# vf_zes.net
KiCad netlist of a schematic drawn in EAGLE
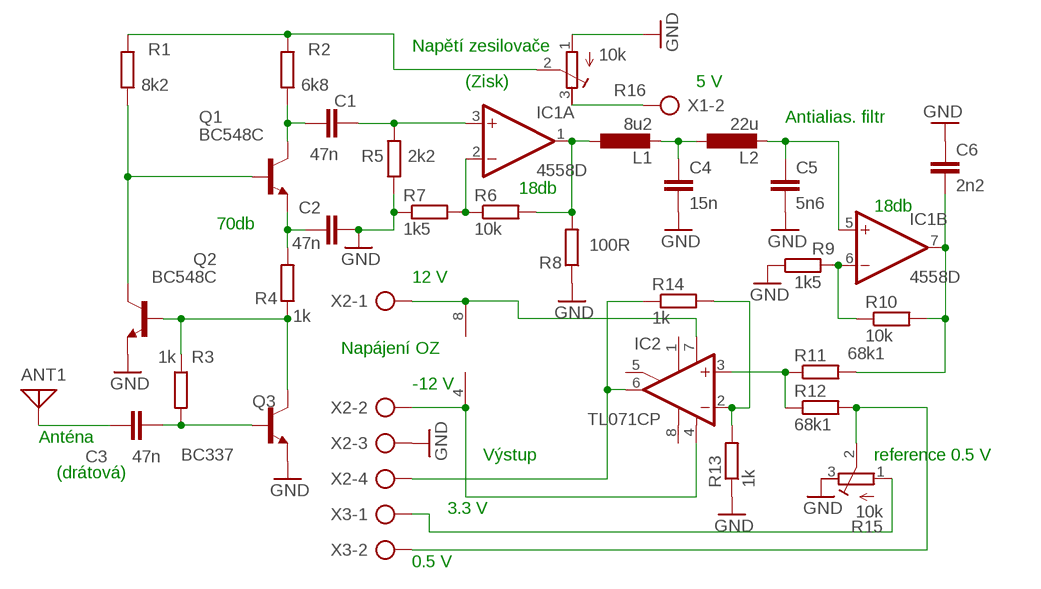
[diagram p0: schematic, sheet 1]

(export (version "E")
  (design (tool "Eeschema 10.0.6"))
  (components
    (comp (ref "ANT1")
      (value "ANTENNA")
      (footprint "eagle-import:PAD-01")
      (libsource (lib "eagle-import") (part "ANTENNA"))
    )
    (comp (ref "C1")
      (value "47n")
      (footprint "eagle-import:C025-025X050")
      (libsource (lib "eagle-import") (part "resistor_C-EU025-025X050"))
    )
    (comp (ref "C2")
      (value "47n")
      (footprint "eagle-import:C025-025X050")
      (libsource (lib "eagle-import") (part "resistor_C-EU025-025X050"))
    )
    (comp (ref "C3")
      (value "47n")
      (footprint "eagle-import:C025-025X050")
      (libsource (lib "eagle-import") (part "resistor_C-EU025-025X050"))
    )
    (comp (ref "C4")
      (value "15n")
      (footprint "eagle-import:C050-025X075")
      (libsource (lib "eagle-import") (part "C-EU050-025X075"))
    )
    (comp (ref "C5")
      (value "5n6")
      (footprint "eagle-import:C050-025X075")
      (libsource (lib "eagle-import") (part "C-EU050-025X075"))
    )
    (comp (ref "C6")
      (value "2n2")
      (footprint "eagle-import:C050-030X075")
      (libsource (lib "eagle-import") (part "C-EU050-030X075"))
    )
    (comp (ref "IC1")
      (value "4558D")
      (footprint "eagle-import:DIL08")
      (libsource (lib "eagle-import") (part "LF442N"))
    )
    (comp (ref "IC2")
      (value "TL071CP")
      (footprint "eagle-import:DIL08")
      (libsource (lib "eagle-import") (part "TL071P"))
    )
    (comp (ref "L1")
      (value "8u2")
      (footprint "eagle-import:0207_12")
      (libsource (lib "eagle-import") (part "L-EU0207/12"))
    )
    (comp (ref "L2")
      (value "22u")
      (footprint "eagle-import:0207_12")
      (libsource (lib "eagle-import") (part "L-EU0207/12"))
    )
    (comp (ref "Q1")
      (value "BC548C")
      (footprint "eagle-import:TO92-EBC")
      (libsource (lib "eagle-import") (part "BC548A"))
    )
    (comp (ref "Q2")
      (value "BC548C")
      (footprint "eagle-import:TO92-EBC")
      (libsource (lib "eagle-import") (part "BC548A"))
    )
    (comp (ref "Q3")
      (value "BC337")
      (footprint "eagle-import:TO92-EBC")
      (libsource (lib "eagle-import") (part "BC548A"))
    )
    (comp (ref "R1")
      (value "8k2")
      (footprint "eagle-import:0207_10")
      (libsource (lib "eagle-import") (part "resistor_R-EU_0207/10"))
    )
    (comp (ref "R2")
      (value "6k8")
      (footprint "eagle-import:0207_10")
      (libsource (lib "eagle-import") (part "resistor_R-EU_0207/10"))
    )
    (comp (ref "R3")
      (value "1k")
      (footprint "eagle-import:0207_10")
      (libsource (lib "eagle-import") (part "resistor_R-EU_0207/10"))
    )
    (comp (ref "R4")
      (value "1k")
      (footprint "eagle-import:0207_10")
      (libsource (lib "eagle-import") (part "resistor_R-EU_0207/10"))
    )
    (comp (ref "R5")
      (value "2k2")
      (footprint "eagle-import:0207_10")
      (libsource (lib "eagle-import") (part "R-EU_0207/10"))
    )
    (comp (ref "R6")
      (value "10k")
      (footprint "eagle-import:0207_10")
      (libsource (lib "eagle-import") (part "R-EU_0207/10"))
    )
    (comp (ref "R7")
      (value "1k5")
      (footprint "eagle-import:0207_10")
      (libsource (lib "eagle-import") (part "R-EU_0207/10"))
    )
    (comp (ref "R8")
      (value "100R")
      (footprint "eagle-import:0207_10")
      (libsource (lib "eagle-import") (part "R-EU_0207/10"))
    )
    (comp (ref "R9")
      (value "1k5")
      (footprint "eagle-import:0207_10")
      (libsource (lib "eagle-import") (part "R-EU_0207/10"))
    )
    (comp (ref "R10")
      (value "10k")
      (footprint "eagle-import:0207_10")
      (libsource (lib "eagle-import") (part "R-EU_0207/10"))
    )
    (comp (ref "R11")
      (value "68k1")
      (footprint "eagle-import:0309_12")
      (libsource (lib "eagle-import") (part "R-EU_0309/12"))
    )
    (comp (ref "R12")
      (value "68k1")
      (footprint "eagle-import:0309_12")
      (libsource (lib "eagle-import") (part "R-EU_0309/12"))
    )
    (comp (ref "R13")
      (value "1k")
      (footprint "eagle-import:0309_12")
      (libsource (lib "eagle-import") (part "R-EU_0309/12"))
    )
    (comp (ref "R14")
      (value "1k")
      (footprint "eagle-import:0309_12")
      (libsource (lib "eagle-import") (part "R-EU_0309/12"))
    )
    (comp (ref "R15")
      (value "10k")
      (footprint "eagle-import:RTRIM64W")
      (libsource (lib "eagle-import") (part "resistor_R-TRIMM64W"))
    )
    (comp (ref "R16")
      (value "10k")
      (footprint "eagle-import:RTRIM64X")
      (libsource (lib "eagle-import") (part "R-TRIMM64X"))
    )
    (comp (ref "X1")
      (value "AK300/2")
      (footprint "eagle-import:AK300_2")
      (libsource (lib "eagle-import") (part "AK300/2"))
    )
    (comp (ref "X2")
      (value "AK500/4-H")
      (footprint "eagle-import:AK500_4-H")
      (libsource (lib "eagle-import") (part "AK500/4-H"))
    )
    (comp (ref "X3")
      (value "AK500/2-H")
      (footprint "eagle-import:AK500_2-H")
      (libsource (lib "eagle-import") (part "AK500/2-H"))
    )
  )
  (nets
    (net (code "1") (name "GND") (class "Default")
      (node (ref "C2") (pin "2") (pinfunction "2_2") (pintype "passive"))
      (node (ref "C4") (pin "2") (pinfunction "2_2") (pintype "passive"))
      (node (ref "C5") (pin "2") (pinfunction "2_2") (pintype "passive"))
      (node (ref "C6") (pin "1") (pinfunction "1_1") (pintype "passive"))
      (node (ref "Q2") (pin "E") (pinfunction "E_E") (pintype "passive"))
      (node (ref "Q3") (pin "E") (pinfunction "E_E") (pintype "passive"))
      (node (ref "R13") (pin "1") (pinfunction "1_1") (pintype "passive"))
      (node (ref "R15") (pin "3") (pinfunction "A_3") (pintype "passive"))
      (node (ref "R16") (pin "1") (pinfunction "A_1") (pintype "passive"))
      (node (ref "R5") (pin "1") (pinfunction "1_1") (pintype "passive"))
      (node (ref "R7") (pin "1") (pinfunction "1_1") (pintype "passive"))
      (node (ref "R8") (pin "1") (pinfunction "1_1") (pintype "passive"))
      (node (ref "R9") (pin "1") (pinfunction "1_1") (pintype "passive"))
      (node (ref "X2") (pin "3") (pinfunction "KL_3") (pintype "passive"))
    )
    (net (code "2") (name "Net-(ANT1-Pad1)") (class "Default")
      (node (ref "ANT1") (pin "1") (pinfunction "1_1") (pintype "output"))
      (node (ref "C3") (pin "1") (pinfunction "1_1") (pintype "passive"))
    )
    (net (code "3") (name "Net-(C1-Pad1)") (class "Default")
      (node (ref "C1") (pin "1") (pinfunction "1_1") (pintype "passive"))
      (node (ref "Q1") (pin "C") (pinfunction "C_C") (pintype "passive"))
      (node (ref "R2") (pin "1") (pinfunction "1_1") (pintype "passive"))
    )
    (net (code "4") (name "Net-(C2-Pad1)") (class "Default")
      (node (ref "C2") (pin "1") (pinfunction "1_1") (pintype "passive"))
      (node (ref "Q1") (pin "E") (pinfunction "E_E") (pintype "passive"))
      (node (ref "R4") (pin "2") (pinfunction "2_2") (pintype "passive"))
    )
    (net (code "5") (name "Net-(C3-Pad2)") (class "Default")
      (node (ref "C3") (pin "2") (pinfunction "2_2") (pintype "passive"))
      (node (ref "Q3") (pin "B") (pinfunction "B_B") (pintype "passive"))
      (node (ref "R3") (pin "2") (pinfunction "2_2") (pintype "passive"))
    )
    (net (code "6") (name "Net-(C4-Pad1)") (class "Default")
      (node (ref "C4") (pin "1") (pinfunction "1_1") (pintype "passive"))
      (node (ref "L1") (pin "2") (pinfunction "2_2") (pintype "passive"))
      (node (ref "L2") (pin "1") (pinfunction "1_1") (pintype "passive"))
    )
    (net (code "7") (name "Net-(IC1A-+IN)") (class "Default")
      (node (ref "C1") (pin "2") (pinfunction "2_2") (pintype "passive"))
      (node (ref "IC1") (pin "3") (pinfunction "+IN_3") (pintype "input"))
      (node (ref "R5") (pin "2") (pinfunction "2_2") (pintype "passive"))
    )
    (net (code "8") (name "Net-(IC1A--IN)") (class "Default")
      (node (ref "IC1") (pin "2") (pinfunction "-IN_2") (pintype "input"))
      (node (ref "R6") (pin "1") (pinfunction "1_1") (pintype "passive"))
      (node (ref "R7") (pin "2") (pinfunction "2_2") (pintype "passive"))
    )
    (net (code "9") (name "Net-(IC1A-OUT)") (class "Default")
      (node (ref "IC1") (pin "1") (pinfunction "OUT_1") (pintype "output"))
      (node (ref "L1") (pin "1") (pinfunction "1_1") (pintype "passive"))
      (node (ref "R6") (pin "2") (pinfunction "2_2") (pintype "passive"))
      (node (ref "R8") (pin "2") (pinfunction "2_2") (pintype "passive"))
    )
    (net (code "10") (name "Net-(IC1B-+IN)") (class "Default")
      (node (ref "C5") (pin "1") (pinfunction "1_1") (pintype "passive"))
      (node (ref "IC1") (pin "5") (pinfunction "+IN_5") (pintype "input"))
      (node (ref "L2") (pin "2") (pinfunction "2_2") (pintype "passive"))
    )
    (net (code "11") (name "Net-(IC1B--IN)") (class "Default")
      (node (ref "IC1") (pin "6") (pinfunction "-IN_6") (pintype "input"))
      (node (ref "R10") (pin "1") (pinfunction "1_1") (pintype "passive"))
      (node (ref "R9") (pin "2") (pinfunction "2_2") (pintype "passive"))
    )
    (net (code "12") (name "Net-(IC1B-OUT)") (class "Default")
      (node (ref "C6") (pin "2") (pinfunction "2_2") (pintype "passive"))
      (node (ref "IC1") (pin "7") (pinfunction "OUT_7") (pintype "output"))
      (node (ref "R10") (pin "2") (pinfunction "2_2") (pintype "passive"))
      (node (ref "R11") (pin "2") (pinfunction "2_2") (pintype "passive"))
    )
    (net (code "13") (name "Net-(IC1C-V+)") (class "Default")
      (node (ref "IC1") (pin "8") (pinfunction "V+_8") (pintype "power_in"))
      (node (ref "IC2") (pin "7") (pinfunction "V+_7") (pintype "power_in"))
      (node (ref "X2") (pin "1") (pinfunction "KL_1") (pintype "passive"))
    )
    (net (code "14") (name "Net-(IC1C-V-)") (class "Default")
      (node (ref "IC1") (pin "4") (pinfunction "V-_4") (pintype "power_in"))
      (node (ref "IC2") (pin "4") (pinfunction "V-_4") (pintype "power_in"))
      (node (ref "X2") (pin "2") (pinfunction "KL_2") (pintype "passive"))
    )
    (net (code "15") (name "Net-(IC2-+IN)") (class "Default")
      (node (ref "IC2") (pin "3") (pinfunction "+IN_3") (pintype "input"))
      (node (ref "R11") (pin "1") (pinfunction "1_1") (pintype "passive"))
      (node (ref "R12") (pin "1") (pinfunction "1_1") (pintype "passive"))
    )
    (net (code "16") (name "Net-(IC2--IN)") (class "Default")
      (node (ref "IC2") (pin "2") (pinfunction "-IN_2") (pintype "input"))
      (node (ref "R13") (pin "2") (pinfunction "2_2") (pintype "passive"))
      (node (ref "R14") (pin "2") (pinfunction "2_2") (pintype "passive"))
    )
    (net (code "17") (name "Net-(IC2-OUT)") (class "Default")
      (node (ref "IC2") (pin "6") (pinfunction "OUT_6") (pintype "output"))
      (node (ref "R14") (pin "1") (pinfunction "1_1") (pintype "passive"))
      (node (ref "X2") (pin "4") (pinfunction "KL_4") (pintype "passive"))
    )
    (net (code "18") (name "Net-(Q1-PadB)") (class "Default")
      (node (ref "Q1") (pin "B") (pinfunction "B_B") (pintype "passive"))
      (node (ref "Q2") (pin "C") (pinfunction "C_C") (pintype "passive"))
      (node (ref "R1") (pin "1") (pinfunction "1_1") (pintype "passive"))
    )
    (net (code "19") (name "Net-(Q2-PadB)") (class "Default")
      (node (ref "Q2") (pin "B") (pinfunction "B_B") (pintype "passive"))
      (node (ref "Q3") (pin "C") (pinfunction "C_C") (pintype "passive"))
      (node (ref "R3") (pin "1") (pinfunction "1_1") (pintype "passive"))
      (node (ref "R4") (pin "1") (pinfunction "1_1") (pintype "passive"))
    )
    (net (code "20") (name "Net-(R15-E)") (class "Default")
      (node (ref "R15") (pin "1") (pinfunction "E_1") (pintype "passive"))
      (node (ref "X3") (pin "1") (pinfunction "KL_1") (pintype "passive"))
    )
    (net (code "21") (name "Net-(R15-S)") (class "Default")
      (node (ref "R12") (pin "2") (pinfunction "2_2") (pintype "passive"))
      (node (ref "R15") (pin "2") (pinfunction "S_2") (pintype "passive"))
      (node (ref "X3") (pin "2") (pinfunction "KL_2") (pintype "passive"))
    )
    (net (code "22") (name "Net-(R16-E)") (class "Default")
      (node (ref "R16") (pin "3") (pinfunction "E_3") (pintype "passive"))
      (node (ref "X1") (pin "2") (pinfunction "KL_2") (pintype "passive"))
    )
    (net (code "23") (name "Net-(R16-S)") (class "Default")
      (node (ref "R1") (pin "2") (pinfunction "2_2") (pintype "passive"))
      (node (ref "R16") (pin "2") (pinfunction "S_2") (pintype "passive"))
      (node (ref "R2") (pin "2") (pinfunction "2_2") (pintype "passive"))
    )
    (net (code "24") (name "unconnected-(IC2-ON1-Pad1)") (class "Default")
      (node (ref "IC2") (pin "1") (pinfunction "ON1_1") (pintype "passive"))
    )
    (net (code "25") (name "unconnected-(IC2-ON2-Pad5)") (class "Default")
      (node (ref "IC2") (pin "5") (pinfunction "ON2_5") (pintype "passive"))
    )
    (net (code "26") (name "unconnected-(IC2-OPT-Pad8)") (class "Default")
      (node (ref "IC2") (pin "8") (pinfunction "OPT_8") (pintype "passive"))
    )
  )
)
